# rapidshark-lipo-sensor-mk-3_6.net
KiCad netlist of a schematic drawn in EAGLE
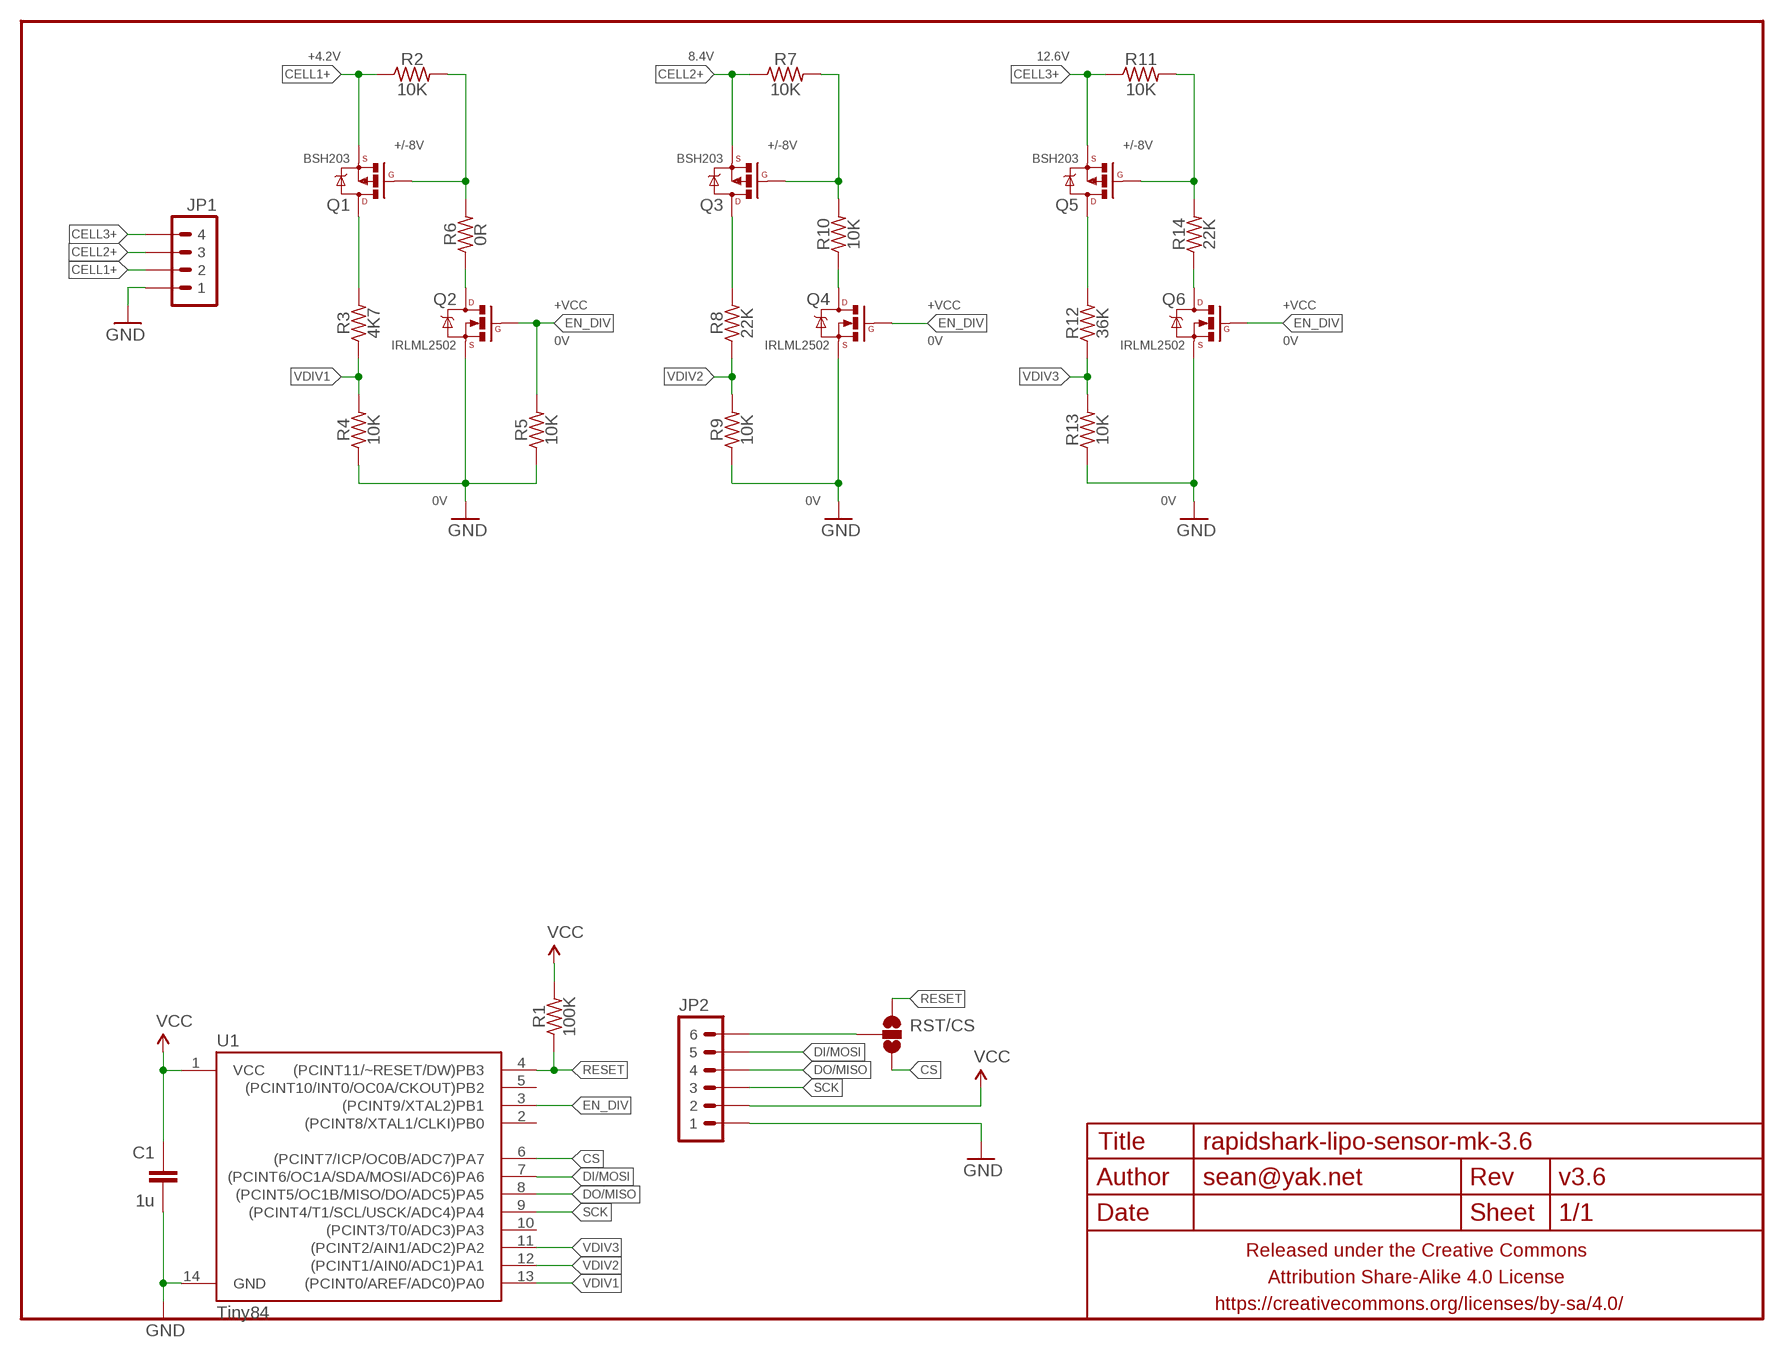
[diagram p0: schematic, sheet 1]

(export (version "E")
  (design (tool "Eeschema 10.0.6"))
  (components
    (comp (ref "C1")
      (value "1u")
      (footprint "eagle-import:C0603-TIGHTER")
      (libsource (lib "eagle-import") (part "CAPACITOR-CERAMICC0603-TIGHTER"))
    )
    (comp (ref "FRAME1")
      (value "FRAME-LETTERNO_PACKAGE")
      (footprint "eagle-import:DUMMY")
      (fields (field (name "DESIGNER") "sean@yak.net") (field (name "VERSION") "v3.6"))
      (libsource (lib "eagle-import") (part "FRAME-LETTERNO_PACKAGE"))
    )
    (comp (ref "JP1")
      (value "M04JST_XH_RA")
      (footprint "eagle-import:JST-4-XH-RA-PTH")
      (libsource (lib "eagle-import") (part "M04JST_XH_RA"))
    )
    (comp (ref "JP2")
      (value "M06PTH_CENTERED")
      (footprint "eagle-import:1X06_CENTERED")
      (libsource (lib "eagle-import") (part "M06PTH_CENTERED"))
    )
    (comp (ref "Q1")
      (value "BSH203")
      (footprint "eagle-import:SOT23")
      (libsource (lib "eagle-import") (part "MOSFET-PCHANNELSOT-23"))
    )
    (comp (ref "Q2")
      (value "IRLML2502")
      (footprint "eagle-import:SOT23")
      (libsource (lib "eagle-import") (part "MOSFET-NCHANNELIRLML2502"))
    )
    (comp (ref "Q3")
      (value "BSH203")
      (footprint "eagle-import:SOT23")
      (libsource (lib "eagle-import") (part "MOSFET-PCHANNELSOT-23"))
    )
    (comp (ref "Q4")
      (value "IRLML2502")
      (footprint "eagle-import:SOT23")
      (libsource (lib "eagle-import") (part "MOSFET-NCHANNELIRLML2502"))
    )
    (comp (ref "Q5")
      (value "BSH203")
      (footprint "eagle-import:SOT23")
      (libsource (lib "eagle-import") (part "MOSFET-PCHANNELSOT-23"))
    )
    (comp (ref "Q6")
      (value "IRLML2502")
      (footprint "eagle-import:SOT23")
      (libsource (lib "eagle-import") (part "MOSFET-NCHANNELIRLML2502"))
    )
    (comp (ref "R1")
      (value "100K")
      (footprint "eagle-import:R0603-TIGHTER")
      (libsource (lib "eagle-import") (part "RESISTORR0603-TIGHTER"))
    )
    (comp (ref "R2")
      (value "10K")
      (footprint "eagle-import:R0603-TIGHTER")
      (libsource (lib "eagle-import") (part "RESISTORR0603-TIGHTER"))
    )
    (comp (ref "R3")
      (value "4K7")
      (footprint "eagle-import:R0603-TIGHTER")
      (libsource (lib "eagle-import") (part "RESISTORR0603-TIGHTER"))
    )
    (comp (ref "R4")
      (value "10K")
      (footprint "eagle-import:R0603-TIGHTER")
      (libsource (lib "eagle-import") (part "RESISTORR0603-TIGHTER"))
    )
    (comp (ref "R5")
      (value "10K")
      (footprint "eagle-import:R0603-TIGHTER")
      (libsource (lib "eagle-import") (part "RESISTORR0603-TIGHTER"))
    )
    (comp (ref "R6")
      (value "0R")
      (footprint "eagle-import:R0603-TIGHTER")
      (libsource (lib "eagle-import") (part "RESISTORR0603-TIGHTER"))
    )
    (comp (ref "R7")
      (value "10K")
      (footprint "eagle-import:R0603-TIGHTER")
      (libsource (lib "eagle-import") (part "RESISTORR0603-TIGHTER"))
    )
    (comp (ref "R8")
      (value "22K")
      (footprint "eagle-import:R0603-TIGHTER")
      (libsource (lib "eagle-import") (part "RESISTORR0603-TIGHTER"))
    )
    (comp (ref "R9")
      (value "10K")
      (footprint "eagle-import:R0603-TIGHTER")
      (libsource (lib "eagle-import") (part "RESISTORR0603-TIGHTER"))
    )
    (comp (ref "R10")
      (value "10K")
      (footprint "eagle-import:R0603-TIGHTER")
      (libsource (lib "eagle-import") (part "RESISTORR0603-TIGHTER"))
    )
    (comp (ref "R11")
      (value "10K")
      (footprint "eagle-import:R0603-TIGHTER")
      (libsource (lib "eagle-import") (part "RESISTORR0603-TIGHTER"))
    )
    (comp (ref "R12")
      (value "36K")
      (footprint "eagle-import:R0603-TIGHTER")
      (libsource (lib "eagle-import") (part "RESISTORR0603-TIGHTER"))
    )
    (comp (ref "R13")
      (value "10K")
      (footprint "eagle-import:R0603-TIGHTER")
      (libsource (lib "eagle-import") (part "RESISTORR0603-TIGHTER"))
    )
    (comp (ref "R14")
      (value "22K")
      (footprint "eagle-import:R0603-TIGHTER")
      (libsource (lib "eagle-import") (part "RESISTORR0603-TIGHTER"))
    )
    (comp (ref "RST/CS")
      (value "JUMPER-PAD-3-NOFULL_BOX_SILK")
      (footprint "eagle-import:PAD-JUMPER-3-NO_YES_SILK_FULL_BOX")
      (libsource (lib "eagle-import") (part "JUMPER-PAD-3-NOFULL_BOX_SILK"))
    )
    (comp (ref "U1")
      (value "Tiny84")
      (footprint "eagle-import:SO14")
      (libsource (lib "eagle-import") (part "ATTINY84"))
    )
  )
  (nets
    (net (code "1") (name "CELL1+") (class "Default")
      (node (ref "JP1") (pin "2") (pinfunction "2_2") (pintype "passive"))
      (node (ref "Q1") (pin "2") (pinfunction "S_2") (pintype "passive"))
      (node (ref "R2") (pin "1") (pinfunction "1_1") (pintype "passive"))
    )
    (net (code "2") (name "CELL2+") (class "Default")
      (node (ref "JP1") (pin "3") (pinfunction "3_3") (pintype "passive"))
      (node (ref "Q3") (pin "2") (pinfunction "S_2") (pintype "passive"))
      (node (ref "R7") (pin "1") (pinfunction "1_1") (pintype "passive"))
    )
    (net (code "3") (name "CELL3+") (class "Default")
      (node (ref "JP1") (pin "4") (pinfunction "4_4") (pintype "passive"))
      (node (ref "Q5") (pin "2") (pinfunction "S_2") (pintype "passive"))
      (node (ref "R11") (pin "1") (pinfunction "1_1") (pintype "passive"))
    )
    (net (code "4") (name "CS") (class "Default")
      (node (ref "RST/CS") (pin "3") (pinfunction "3_3") (pintype "passive"))
      (node (ref "U1") (pin "6") (pinfunction "(PCINT7/ICP/OC0B/ADC7)PA7_6") (pintype "bidirectional"))
    )
    (net (code "5") (name "DI{slash}MOSI") (class "Default")
      (node (ref "JP2") (pin "5") (pinfunction "5_5") (pintype "passive"))
      (node (ref "U1") (pin "7") (pinfunction "(PCINT6/OC1A/SDA/MOSI/ADC6)PA6_7") (pintype "bidirectional"))
    )
    (net (code "6") (name "DO{slash}MISO") (class "Default")
      (node (ref "JP2") (pin "4") (pinfunction "4_4") (pintype "passive"))
      (node (ref "U1") (pin "8") (pinfunction "(PCINT5/OC1B/MISO/DO/ADC5)PA5_8") (pintype "bidirectional"))
    )
    (net (code "7") (name "EN_DIV") (class "Default")
      (node (ref "Q2") (pin "1") (pinfunction "G_1") (pintype "passive"))
      (node (ref "Q4") (pin "1") (pinfunction "G_1") (pintype "passive"))
      (node (ref "Q6") (pin "1") (pinfunction "G_1") (pintype "passive"))
      (node (ref "R5") (pin "2") (pinfunction "2_2") (pintype "passive"))
      (node (ref "U1") (pin "3") (pinfunction "(PCINT9/XTAL2)PB1_3") (pintype "bidirectional"))
    )
    (net (code "8") (name "GND") (class "Default")
      (node (ref "C1") (pin "2") (pinfunction "2_2") (pintype "passive"))
      (node (ref "JP1") (pin "1") (pinfunction "1_1") (pintype "passive"))
      (node (ref "JP2") (pin "1") (pinfunction "1_1") (pintype "passive"))
      (node (ref "Q2") (pin "2") (pinfunction "S_2") (pintype "passive"))
      (node (ref "Q4") (pin "2") (pinfunction "S_2") (pintype "passive"))
      (node (ref "Q6") (pin "2") (pinfunction "S_2") (pintype "passive"))
      (node (ref "R13") (pin "1") (pinfunction "1_1") (pintype "passive"))
      (node (ref "R4") (pin "1") (pinfunction "1_1") (pintype "passive"))
      (node (ref "R5") (pin "1") (pinfunction "1_1") (pintype "passive"))
      (node (ref "R9") (pin "1") (pinfunction "1_1") (pintype "passive"))
      (node (ref "U1") (pin "14") (pinfunction "GND_14") (pintype "bidirectional"))
    )
    (net (code "9") (name "Net-(JP2-Pad6)") (class "Default")
      (node (ref "JP2") (pin "6") (pinfunction "6_6") (pintype "passive"))
      (node (ref "RST/CS") (pin "2") (pinfunction "2_2") (pintype "passive"))
    )
    (net (code "10") (name "Net-(Q1-D)") (class "Default")
      (node (ref "Q1") (pin "3") (pinfunction "D_3") (pintype "passive"))
      (node (ref "R3") (pin "2") (pinfunction "2_2") (pintype "passive"))
    )
    (net (code "11") (name "Net-(Q1-G)") (class "Default")
      (node (ref "Q1") (pin "1") (pinfunction "G_1") (pintype "passive"))
      (node (ref "R2") (pin "2") (pinfunction "2_2") (pintype "passive"))
      (node (ref "R6") (pin "2") (pinfunction "2_2") (pintype "passive"))
    )
    (net (code "12") (name "Net-(Q2-D)") (class "Default")
      (node (ref "Q2") (pin "3") (pinfunction "D_3") (pintype "passive"))
      (node (ref "R6") (pin "1") (pinfunction "1_1") (pintype "passive"))
    )
    (net (code "13") (name "Net-(Q3-D)") (class "Default")
      (node (ref "Q3") (pin "3") (pinfunction "D_3") (pintype "passive"))
      (node (ref "R8") (pin "2") (pinfunction "2_2") (pintype "passive"))
    )
    (net (code "14") (name "Net-(Q3-G)") (class "Default")
      (node (ref "Q3") (pin "1") (pinfunction "G_1") (pintype "passive"))
      (node (ref "R10") (pin "2") (pinfunction "2_2") (pintype "passive"))
      (node (ref "R7") (pin "2") (pinfunction "2_2") (pintype "passive"))
    )
    (net (code "15") (name "Net-(Q4-D)") (class "Default")
      (node (ref "Q4") (pin "3") (pinfunction "D_3") (pintype "passive"))
      (node (ref "R10") (pin "1") (pinfunction "1_1") (pintype "passive"))
    )
    (net (code "16") (name "Net-(Q5-D)") (class "Default")
      (node (ref "Q5") (pin "3") (pinfunction "D_3") (pintype "passive"))
      (node (ref "R12") (pin "2") (pinfunction "2_2") (pintype "passive"))
    )
    (net (code "17") (name "Net-(Q5-G)") (class "Default")
      (node (ref "Q5") (pin "1") (pinfunction "G_1") (pintype "passive"))
      (node (ref "R11") (pin "2") (pinfunction "2_2") (pintype "passive"))
      (node (ref "R14") (pin "2") (pinfunction "2_2") (pintype "passive"))
    )
    (net (code "18") (name "Net-(Q6-D)") (class "Default")
      (node (ref "Q6") (pin "3") (pinfunction "D_3") (pintype "passive"))
      (node (ref "R14") (pin "1") (pinfunction "1_1") (pintype "passive"))
    )
    (net (code "19") (name "RESET") (class "Default")
      (node (ref "R1") (pin "1") (pinfunction "1_1") (pintype "passive"))
      (node (ref "RST/CS") (pin "1") (pinfunction "1_1") (pintype "passive"))
      (node (ref "U1") (pin "4") (pinfunction "(PCINT11/~{RESET/DW})PB3_4") (pintype "bidirectional"))
    )
    (net (code "20") (name "SCK") (class "Default")
      (node (ref "JP2") (pin "3") (pinfunction "3_3") (pintype "passive"))
      (node (ref "U1") (pin "9") (pinfunction "(PCINT4/T1/SCL/USCK/ADC4)PA4_9") (pintype "bidirectional"))
    )
    (net (code "21") (name "VCC") (class "Default")
      (node (ref "C1") (pin "1") (pinfunction "1_1") (pintype "passive"))
      (node (ref "JP2") (pin "2") (pinfunction "2_2") (pintype "passive"))
      (node (ref "R1") (pin "2") (pinfunction "2_2") (pintype "passive"))
      (node (ref "U1") (pin "1") (pinfunction "VCC_1") (pintype "bidirectional"))
    )
    (net (code "22") (name "VDIV1") (class "Default")
      (node (ref "R3") (pin "1") (pinfunction "1_1") (pintype "passive"))
      (node (ref "R4") (pin "2") (pinfunction "2_2") (pintype "passive"))
      (node (ref "U1") (pin "13") (pinfunction "(PCINT0/AREF/ADC0)PA0_13") (pintype "bidirectional"))
    )
    (net (code "23") (name "VDIV2") (class "Default")
      (node (ref "R8") (pin "1") (pinfunction "1_1") (pintype "passive"))
      (node (ref "R9") (pin "2") (pinfunction "2_2") (pintype "passive"))
      (node (ref "U1") (pin "12") (pinfunction "(PCINT1/AIN0/ADC1)PA1_12") (pintype "bidirectional"))
    )
    (net (code "24") (name "VDIV3") (class "Default")
      (node (ref "R12") (pin "1") (pinfunction "1_1") (pintype "passive"))
      (node (ref "R13") (pin "2") (pinfunction "2_2") (pintype "passive"))
      (node (ref "U1") (pin "11") (pinfunction "(PCINT2/AIN1/ADC2)PA2_11") (pintype "bidirectional"))
    )
    (net (code "25") (name "unconnected-(U1-(PCINT3{slash}T0{slash}ADC3)PA3-Pad10)") (class "Default")
      (node (ref "U1") (pin "10") (pinfunction "(PCINT3/T0/ADC3)PA3_10") (pintype "bidirectional"))
    )
    (net (code "26") (name "unconnected-(U1-(PCINT8{slash}XTAL1{slash}CLKI)PB0-Pad2)") (class "Default")
      (node (ref "U1") (pin "2") (pinfunction "(PCINT8/XTAL1/CLKI)PB0_2") (pintype "bidirectional"))
    )
    (net (code "27") (name "unconnected-(U1-(PCINT10{slash}INT0{slash}OC0A{slash}CKOUT)PB2-Pad5)") (class "Default")
      (node (ref "U1") (pin "5") (pinfunction "(PCINT10/INT0/OC0A/CKOUT)PB2_5") (pintype "bidirectional"))
    )
  )
)
